# 2023-12-16_LVMi-IonPump-Controller.net
KiCad netlist of a schematic drawn in EAGLE
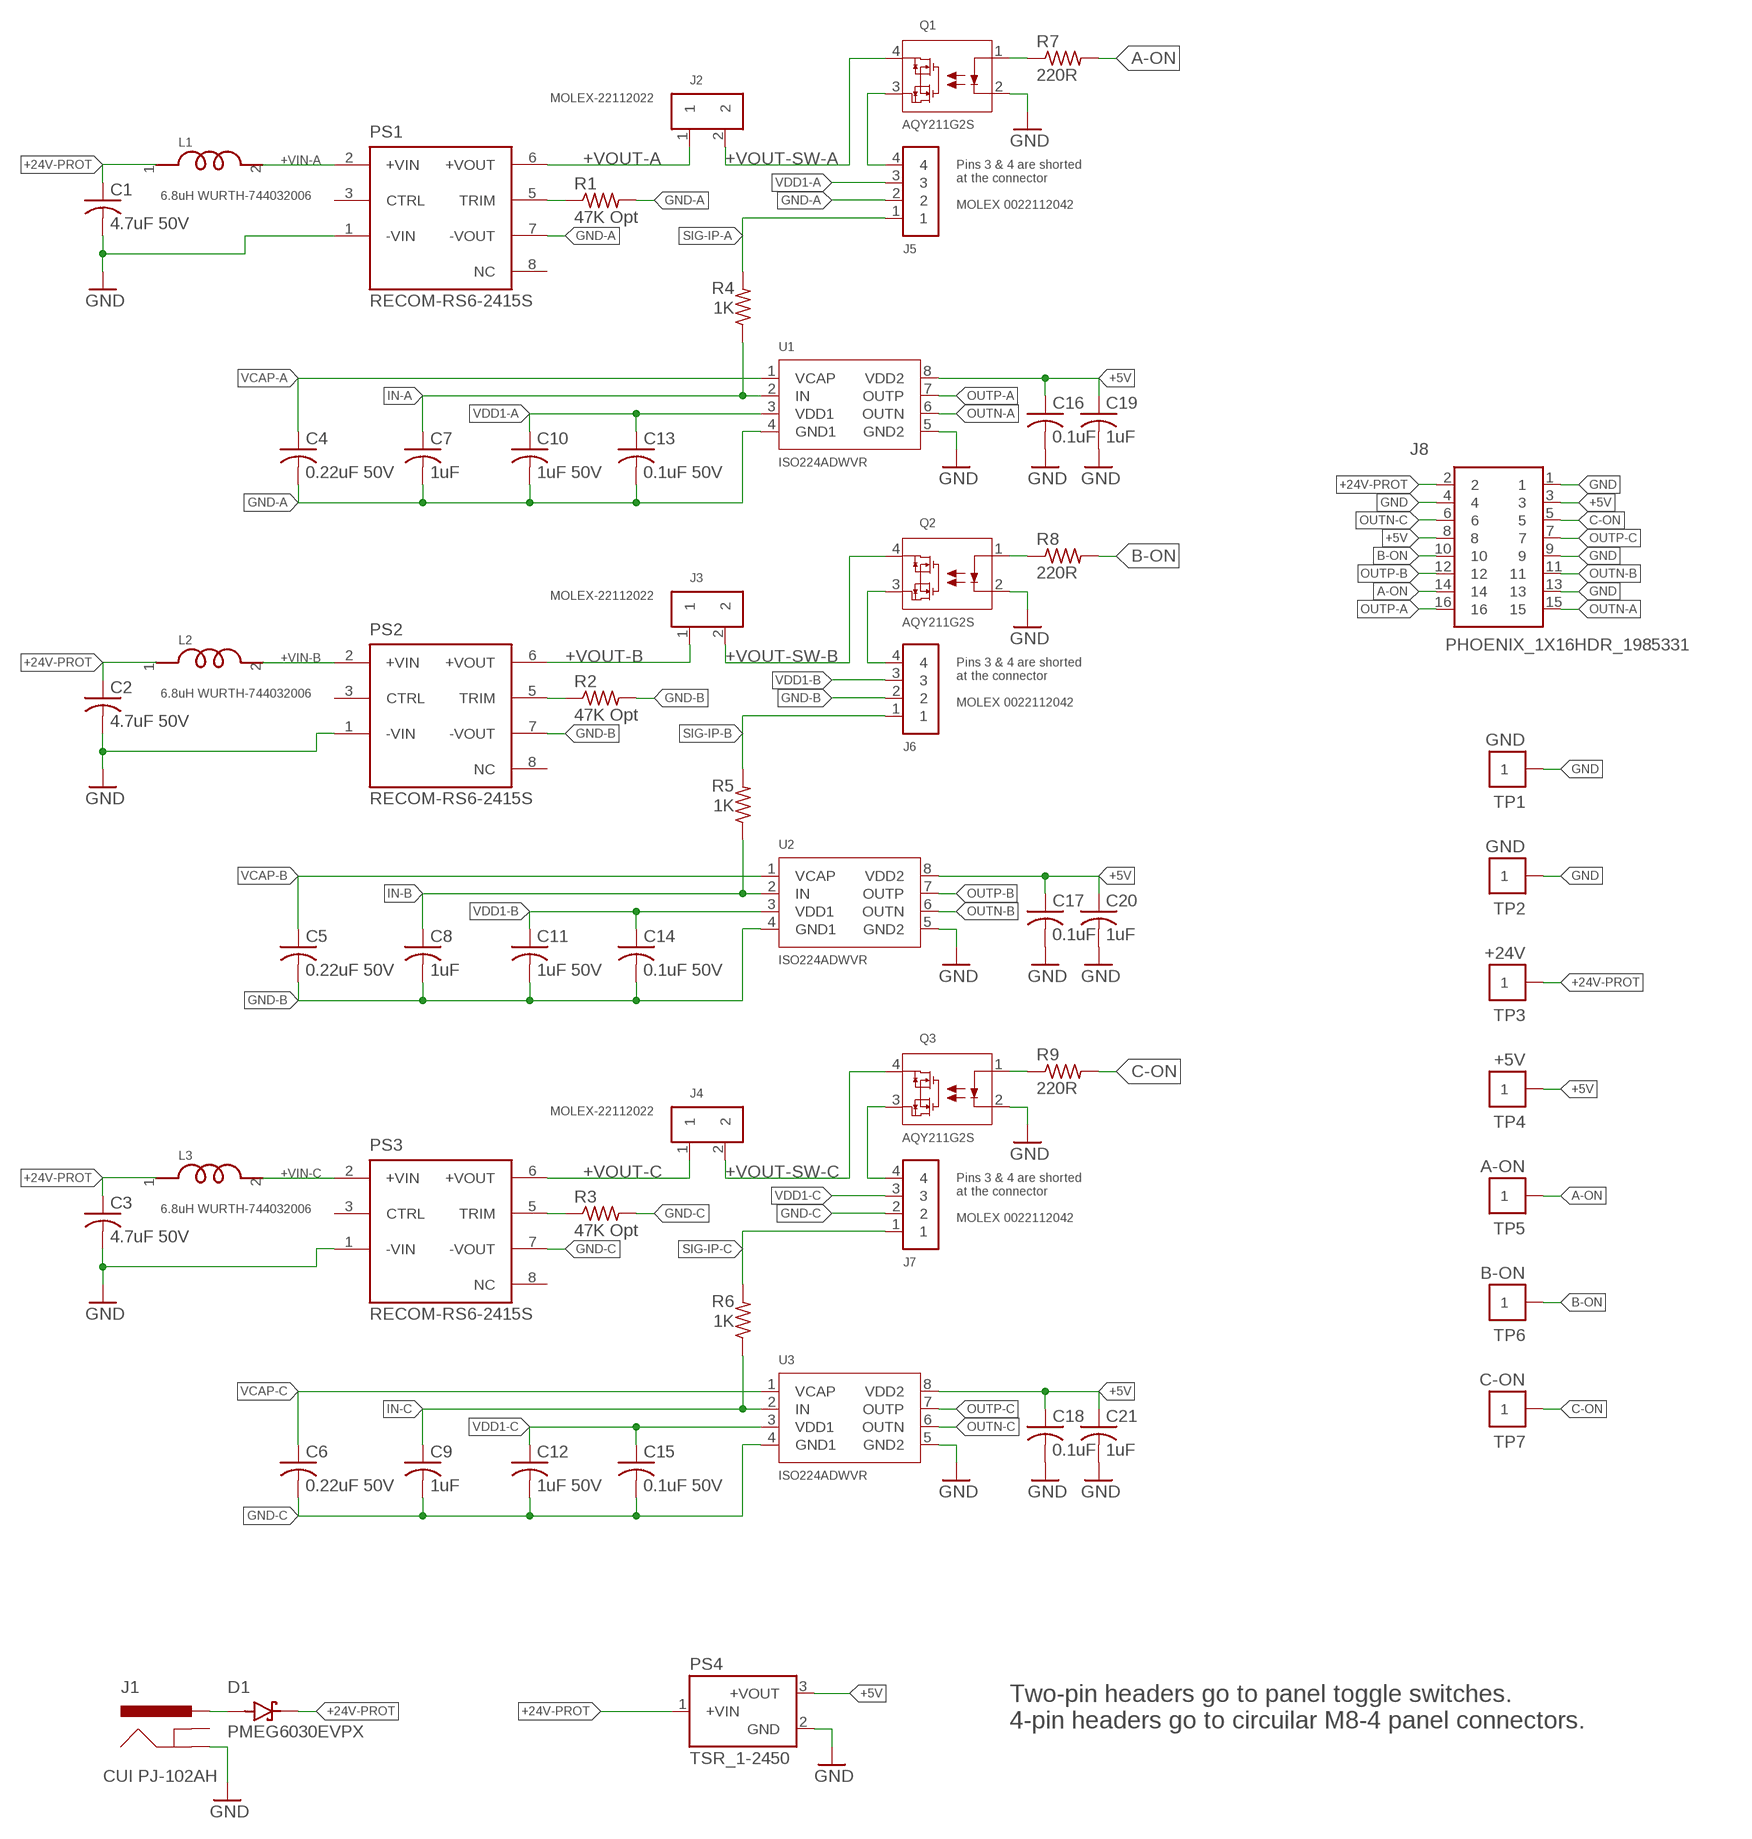
[diagram p0: schematic, sheet 1]

(export (version "E")
  (design (tool "Eeschema 10.0.6"))
  (components
    (comp (ref "C1")
      (value "4.7uF 50V")
      (footprint "eagle-import:C0805")
      (libsource (lib "eagle-import") (part "C-USC0805"))
    )
    (comp (ref "C2")
      (value "4.7uF 50V")
      (footprint "eagle-import:C0805")
      (libsource (lib "eagle-import") (part "C-USC0805"))
    )
    (comp (ref "C3")
      (value "4.7uF 50V")
      (footprint "eagle-import:C0805")
      (libsource (lib "eagle-import") (part "C-USC0805"))
    )
    (comp (ref "C4")
      (value "0.22uF 50V")
      (footprint "eagle-import:C0805")
      (libsource (lib "eagle-import") (part "C-USC0805"))
    )
    (comp (ref "C5")
      (value "0.22uF 50V")
      (footprint "eagle-import:C0805")
      (libsource (lib "eagle-import") (part "C-USC0805"))
    )
    (comp (ref "C6")
      (value "0.22uF 50V")
      (footprint "eagle-import:C0805")
      (libsource (lib "eagle-import") (part "C-USC0805"))
    )
    (comp (ref "C7")
      (value "1uF")
      (footprint "eagle-import:C0805")
      (libsource (lib "eagle-import") (part "C-USC0805"))
    )
    (comp (ref "C8")
      (value "1uF")
      (footprint "eagle-import:C0805")
      (libsource (lib "eagle-import") (part "C-USC0805"))
    )
    (comp (ref "C9")
      (value "1uF")
      (footprint "eagle-import:C0805")
      (libsource (lib "eagle-import") (part "C-USC0805"))
    )
    (comp (ref "C10")
      (value "1uF 50V")
      (footprint "eagle-import:C0805")
      (libsource (lib "eagle-import") (part "C-USC0805"))
    )
    (comp (ref "C11")
      (value "1uF 50V")
      (footprint "eagle-import:C0805")
      (libsource (lib "eagle-import") (part "C-USC0805"))
    )
    (comp (ref "C12")
      (value "1uF 50V")
      (footprint "eagle-import:C0805")
      (libsource (lib "eagle-import") (part "C-USC0805"))
    )
    (comp (ref "C13")
      (value "0.1uF 50V")
      (footprint "eagle-import:C0805")
      (libsource (lib "eagle-import") (part "C-USC0805"))
    )
    (comp (ref "C14")
      (value "0.1uF 50V")
      (footprint "eagle-import:C0805")
      (libsource (lib "eagle-import") (part "C-USC0805"))
    )
    (comp (ref "C15")
      (value "0.1uF 50V")
      (footprint "eagle-import:C0805")
      (libsource (lib "eagle-import") (part "C-USC0805"))
    )
    (comp (ref "C16")
      (value "0.1uF")
      (footprint "eagle-import:C0805")
      (libsource (lib "eagle-import") (part "C-USC0805"))
    )
    (comp (ref "C17")
      (value "0.1uF")
      (footprint "eagle-import:C0805")
      (libsource (lib "eagle-import") (part "C-USC0805"))
    )
    (comp (ref "C18")
      (value "0.1uF")
      (footprint "eagle-import:C0805")
      (libsource (lib "eagle-import") (part "C-USC0805"))
    )
    (comp (ref "C19")
      (value "1uF")
      (footprint "eagle-import:C0805")
      (libsource (lib "eagle-import") (part "C-USC0805"))
    )
    (comp (ref "C20")
      (value "1uF")
      (footprint "eagle-import:C0805")
      (libsource (lib "eagle-import") (part "C-USC0805"))
    )
    (comp (ref "C21")
      (value "1uF")
      (footprint "eagle-import:C0805")
      (libsource (lib "eagle-import") (part "C-USC0805"))
    )
    (comp (ref "D1")
      (value "PMEG6030EVPX")
      (footprint "eagle-import:DIO_PMEG6030EVPX")
      (fields (field (name "DIGI-KEY_PART_NUMBER") "1727-1349-1-ND") (field (name "MF") "Nexperia USA"))
      (libsource (lib "eagle-import") (part "SCHOTTKY-PMEG6030EVPX"))
    )
    (comp (ref "J1")
      (value "CUI PJ-102AH")
      (footprint "eagle-import:PJ-102AH")
      (libsource (lib "eagle-import") (part "POWER_JACKPJ-102AH"))
    )
    (comp (ref "J2")
      (value "MOLEX-22112022")
      (footprint "eagle-import:1X02-MOLEX-22112022")
      (libsource (lib "eagle-import") (part "PINHD-1X2-MOLEX-22112022"))
    )
    (comp (ref "J3")
      (value "MOLEX-22112022")
      (footprint "eagle-import:1X02-MOLEX-22112022")
      (libsource (lib "eagle-import") (part "PINHD-1X2-MOLEX-22112022"))
    )
    (comp (ref "J4")
      (value "MOLEX-22112022")
      (footprint "eagle-import:1X02-MOLEX-22112022")
      (libsource (lib "eagle-import") (part "PINHD-1X2-MOLEX-22112022"))
    )
    (comp (ref "J5")
      (value "MOLEX 0022112042")
      (footprint "eagle-import:1X04-MOLEX-22112042")
      (libsource (lib "eagle-import") (part "PINHD-1X4-MOLEX-22112042"))
    )
    (comp (ref "J6")
      (value "MOLEX 0022112042")
      (footprint "eagle-import:1X04-MOLEX-22112042")
      (libsource (lib "eagle-import") (part "PINHD-1X4-MOLEX-22112042"))
    )
    (comp (ref "J7")
      (value "MOLEX 0022112042")
      (footprint "eagle-import:1X04-MOLEX-22112042")
      (libsource (lib "eagle-import") (part "PINHD-1X4-MOLEX-22112042"))
    )
    (comp (ref "J8")
      (value "PHOENIX_1X16HDR_1985331")
      (footprint "eagle-import:1985331")
      (fields
        (field (name "MANUFACTURER_PART_NUMBER") "1985331")
        (field (name "MOUSER_PART_NUMBER") "651-1985331")
      )
      (libsource (lib "eagle-import") (part "PHOENIX_1X16HDR_1985331"))
    )
    (comp (ref "L1")
      (value "6.8uH WURTH-744032006")
      (footprint "eagle-import:WURTH-1210-INDUCTOR")
      (libsource (lib "eagle-import") (part "INDUCTOR-WURTH-744032006"))
    )
    (comp (ref "L2")
      (value "6.8uH WURTH-744032006")
      (footprint "eagle-import:WURTH-1210-INDUCTOR")
      (libsource (lib "eagle-import") (part "INDUCTOR-WURTH-744032006"))
    )
    (comp (ref "L3")
      (value "6.8uH WURTH-744032006")
      (footprint "eagle-import:WURTH-1210-INDUCTOR")
      (libsource (lib "eagle-import") (part "INDUCTOR-WURTH-744032006"))
    )
    (comp (ref "PS1")
      (value "RECOM-RS6-2415S")
      (footprint "eagle-import:CONV_RS6-2415S")
      (fields
        (field (name "DIGI-KEY_PART_NUMBER") "945-2987-ND")
        (field (name "MF") "Recom Power")
        (field (name "MP") "RS6-2415S")
      )
      (libsource (lib "eagle-import") (part "DC-DC-15V-RECOM-RS6-2415S"))
    )
    (comp (ref "PS2")
      (value "RECOM-RS6-2415S")
      (footprint "eagle-import:CONV_RS6-2415S")
      (fields
        (field (name "DIGI-KEY_PART_NUMBER") "945-2987-ND")
        (field (name "MF") "Recom Power")
        (field (name "MP") "RS6-2415S")
      )
      (libsource (lib "eagle-import") (part "DC-DC-15V-RECOM-RS6-2415S"))
    )
    (comp (ref "PS3")
      (value "RECOM-RS6-2415S")
      (footprint "eagle-import:CONV_RS6-2415S")
      (fields
        (field (name "DIGI-KEY_PART_NUMBER") "945-2987-ND")
        (field (name "MF") "Recom Power")
        (field (name "MP") "RS6-2415S")
      )
      (libsource (lib "eagle-import") (part "DC-DC-15V-RECOM-RS6-2415S"))
    )
    (comp (ref "PS4")
      (value "TSR_1-2450")
      (footprint "eagle-import:CONV_TSR_1-2450")
      (fields (field (name "MANUFACTURER") "Traco Power"))
      (libsource (lib "eagle-import") (part "TSR_1-2450"))
    )
    (comp (ref "Q1")
      (value "AQY211G2S")
      (footprint "eagle-import:SOP4_PAN")
      (fields
        (field (name "MANUFACTURER_PART_NUMBER") "AQY212GSX")
        (field (name "COPYRIGHT") "Copyright (C) 2023 Ultra Librarian. All rights reserved.")
      )
      (libsource (lib "eagle-import") (part "AQY212GSX"))
    )
    (comp (ref "Q2")
      (value "AQY211G2S")
      (footprint "eagle-import:SOP4_PAN")
      (fields
        (field (name "MANUFACTURER_PART_NUMBER") "AQY212GSX")
        (field (name "COPYRIGHT") "Copyright (C) 2023 Ultra Librarian. All rights reserved.")
      )
      (libsource (lib "eagle-import") (part "AQY212GSX"))
    )
    (comp (ref "Q3")
      (value "AQY211G2S")
      (footprint "eagle-import:SOP4_PAN")
      (fields
        (field (name "MANUFACTURER_PART_NUMBER") "AQY212GSX")
        (field (name "COPYRIGHT") "Copyright (C) 2023 Ultra Librarian. All rights reserved.")
      )
      (libsource (lib "eagle-import") (part "AQY212GSX"))
    )
    (comp (ref "R1")
      (value "47K Opt")
      (footprint "eagle-import:R0805")
      (libsource (lib "eagle-import") (part "R-US_R0805"))
    )
    (comp (ref "R2")
      (value "47K Opt")
      (footprint "eagle-import:R0805")
      (libsource (lib "eagle-import") (part "R-US_R0805"))
    )
    (comp (ref "R3")
      (value "47K Opt")
      (footprint "eagle-import:R0805")
      (libsource (lib "eagle-import") (part "R-US_R0805"))
    )
    (comp (ref "R4")
      (value "1K")
      (footprint "eagle-import:R0805")
      (libsource (lib "eagle-import") (part "R-US_R0805"))
    )
    (comp (ref "R5")
      (value "1K")
      (footprint "eagle-import:R0805")
      (libsource (lib "eagle-import") (part "R-US_R0805"))
    )
    (comp (ref "R6")
      (value "1K")
      (footprint "eagle-import:R0805")
      (libsource (lib "eagle-import") (part "R-US_R0805"))
    )
    (comp (ref "R7")
      (value "220R")
      (footprint "eagle-import:R0805")
      (libsource (lib "eagle-import") (part "R-US_R0805"))
    )
    (comp (ref "R8")
      (value "220R")
      (footprint "eagle-import:R0805")
      (libsource (lib "eagle-import") (part "R-US_R0805"))
    )
    (comp (ref "R9")
      (value "220R")
      (footprint "eagle-import:R0805")
      (libsource (lib "eagle-import") (part "R-US_R0805"))
    )
    (comp (ref "TP1")
      (value "GND")
      (footprint "eagle-import:TP5000-TESTPOINT-BLK")
      (libsource (lib "eagle-import") (part "TP5000-TESTPOINT-BLK"))
    )
    (comp (ref "TP2")
      (value "GND")
      (footprint "eagle-import:TP5000-TESTPOINT-BLK")
      (libsource (lib "eagle-import") (part "TP5000-TESTPOINT-BLK"))
    )
    (comp (ref "TP3")
      (value "+24V")
      (footprint "eagle-import:TP5000-TESTPOINT-BLK")
      (libsource (lib "eagle-import") (part "TP5000-TESTPOINT-BLK"))
    )
    (comp (ref "TP4")
      (value "+5V")
      (footprint "eagle-import:TP5000-TESTPOINT-BLK")
      (libsource (lib "eagle-import") (part "TP5000-TESTPOINT-BLK"))
    )
    (comp (ref "TP5")
      (value "A-ON")
      (footprint "eagle-import:TP5000-TESTPOINT-BLK")
      (libsource (lib "eagle-import") (part "TP5000-TESTPOINT-BLK"))
    )
    (comp (ref "TP6")
      (value "B-ON")
      (footprint "eagle-import:TP5000-TESTPOINT-BLK")
      (libsource (lib "eagle-import") (part "TP5000-TESTPOINT-BLK"))
    )
    (comp (ref "TP7")
      (value "C-ON")
      (footprint "eagle-import:TP5000-TESTPOINT-BLK")
      (libsource (lib "eagle-import") (part "TP5000-TESTPOINT-BLK"))
    )
    (comp (ref "U1")
      (value "ISO224ADWVR")
      (footprint "eagle-import:DWV8_TEX")
      (fields (field (name "COPYRIGHT") "Copyright (C) 2018 Accelerated Designs. All rights reserved"))
      (libsource (lib "eagle-import") (part "ISO224ADWVR"))
    )
    (comp (ref "U2")
      (value "ISO224ADWVR")
      (footprint "eagle-import:DWV8_TEX")
      (fields (field (name "COPYRIGHT") "Copyright (C) 2018 Accelerated Designs. All rights reserved"))
      (libsource (lib "eagle-import") (part "ISO224ADWVR"))
    )
    (comp (ref "U3")
      (value "ISO224ADWVR")
      (footprint "eagle-import:DWV8_TEX")
      (fields (field (name "COPYRIGHT") "Copyright (C) 2018 Accelerated Designs. All rights reserved"))
      (libsource (lib "eagle-import") (part "ISO224ADWVR"))
    )
  )
  (nets
    (net (code "1") (name "+5V") (class "Default")
      (node (ref "C16") (pin "1") (pinfunction "1_1") (pintype "passive"))
      (node (ref "C17") (pin "1") (pinfunction "1_1") (pintype "passive"))
      (node (ref "C18") (pin "1") (pinfunction "1_1") (pintype "passive"))
      (node (ref "C19") (pin "1") (pinfunction "1_1") (pintype "passive"))
      (node (ref "C20") (pin "1") (pinfunction "1_1") (pintype "passive"))
      (node (ref "C21") (pin "1") (pinfunction "1_1") (pintype "passive"))
      (node (ref "J8") (pin "3") (pinfunction "3_3") (pintype "bidirectional"))
      (node (ref "J8") (pin "8") (pinfunction "8_8") (pintype "bidirectional"))
      (node (ref "PS4") (pin "3") (pinfunction "+VOUT_3") (pintype "output"))
      (node (ref "TP4") (pin "P$1") (pinfunction "1_P$1") (pintype "bidirectional"))
      (node (ref "U1") (pin "8") (pinfunction "VDD2_8") (pintype "power_in"))
      (node (ref "U2") (pin "8") (pinfunction "VDD2_8") (pintype "power_in"))
      (node (ref "U3") (pin "8") (pinfunction "VDD2_8") (pintype "power_in"))
    )
    (net (code "2") (name "+24V-PROT") (class "Default")
      (node (ref "C1") (pin "1") (pinfunction "1_1") (pintype "passive"))
      (node (ref "C2") (pin "1") (pinfunction "1_1") (pintype "passive"))
      (node (ref "C3") (pin "1") (pinfunction "1_1") (pintype "passive"))
      (node (ref "D1") (pin "1") (pinfunction "K_1") (pintype "passive"))
      (node (ref "J8") (pin "2") (pinfunction "2_2") (pintype "bidirectional"))
      (node (ref "L1") (pin "1") (pinfunction "1_1") (pintype "bidirectional"))
      (node (ref "L2") (pin "1") (pinfunction "1_1") (pintype "bidirectional"))
      (node (ref "L3") (pin "1") (pinfunction "1_1") (pintype "bidirectional"))
      (node (ref "PS4") (pin "1") (pinfunction "+VIN_1") (pintype "input"))
      (node (ref "TP3") (pin "P$1") (pinfunction "1_P$1") (pintype "bidirectional"))
    )
    (net (code "3") (name "/+VIN-A") (class "Default")
      (node (ref "L1") (pin "2") (pinfunction "2_2") (pintype "bidirectional"))
      (node (ref "PS1") (pin "2") (pinfunction "+VIN_2") (pintype "input"))
    )
    (net (code "4") (name "/+VIN-B") (class "Default")
      (node (ref "L2") (pin "2") (pinfunction "2_2") (pintype "bidirectional"))
      (node (ref "PS2") (pin "2") (pinfunction "+VIN_2") (pintype "input"))
    )
    (net (code "5") (name "/+VIN-C") (class "Default")
      (node (ref "L3") (pin "2") (pinfunction "2_2") (pintype "bidirectional"))
      (node (ref "PS3") (pin "2") (pinfunction "+VIN_2") (pintype "input"))
    )
    (net (code "6") (name "/+VOUT-A") (class "Default")
      (node (ref "J2") (pin "1") (pinfunction "1_1") (pintype "bidirectional"))
      (node (ref "PS1") (pin "6") (pinfunction "+VOUT_6") (pintype "output"))
    )
    (net (code "7") (name "/+VOUT-B") (class "Default")
      (node (ref "J3") (pin "1") (pinfunction "1_1") (pintype "bidirectional"))
      (node (ref "PS2") (pin "6") (pinfunction "+VOUT_6") (pintype "output"))
    )
    (net (code "8") (name "/+VOUT-C") (class "Default")
      (node (ref "J4") (pin "1") (pinfunction "1_1") (pintype "bidirectional"))
      (node (ref "PS3") (pin "6") (pinfunction "+VOUT_6") (pintype "output"))
    )
    (net (code "9") (name "/+VOUT-SW-A") (class "Default")
      (node (ref "J2") (pin "2") (pinfunction "2_2") (pintype "bidirectional"))
      (node (ref "Q1") (pin "4") (pinfunction "4_4") (pintype "passive"))
    )
    (net (code "10") (name "/+VOUT-SW-B") (class "Default")
      (node (ref "J3") (pin "2") (pinfunction "2_2") (pintype "bidirectional"))
      (node (ref "Q2") (pin "4") (pinfunction "4_4") (pintype "passive"))
    )
    (net (code "11") (name "/+VOUT-SW-C") (class "Default")
      (node (ref "J4") (pin "2") (pinfunction "2_2") (pintype "bidirectional"))
      (node (ref "Q3") (pin "4") (pinfunction "4_4") (pintype "passive"))
    )
    (net (code "12") (name "A-ON") (class "Default")
      (node (ref "J8") (pin "14") (pinfunction "14_14") (pintype "bidirectional"))
      (node (ref "R7") (pin "2") (pinfunction "2_2") (pintype "passive"))
      (node (ref "TP5") (pin "P$1") (pinfunction "1_P$1") (pintype "bidirectional"))
    )
    (net (code "13") (name "B-ON") (class "Default")
      (node (ref "J8") (pin "10") (pinfunction "10_10") (pintype "bidirectional"))
      (node (ref "R8") (pin "2") (pinfunction "2_2") (pintype "passive"))
      (node (ref "TP6") (pin "P$1") (pinfunction "1_P$1") (pintype "bidirectional"))
    )
    (net (code "14") (name "C-ON") (class "Default")
      (node (ref "J8") (pin "5") (pinfunction "5_5") (pintype "bidirectional"))
      (node (ref "R9") (pin "2") (pinfunction "2_2") (pintype "passive"))
      (node (ref "TP7") (pin "P$1") (pinfunction "1_P$1") (pintype "bidirectional"))
    )
    (net (code "15") (name "GND") (class "Default")
      (node (ref "C1") (pin "2") (pinfunction "2_2") (pintype "passive"))
      (node (ref "C16") (pin "2") (pinfunction "2_2") (pintype "passive"))
      (node (ref "C17") (pin "2") (pinfunction "2_2") (pintype "passive"))
      (node (ref "C18") (pin "2") (pinfunction "2_2") (pintype "passive"))
      (node (ref "C19") (pin "2") (pinfunction "2_2") (pintype "passive"))
      (node (ref "C2") (pin "2") (pinfunction "2_2") (pintype "passive"))
      (node (ref "C20") (pin "2") (pinfunction "2_2") (pintype "passive"))
      (node (ref "C21") (pin "2") (pinfunction "2_2") (pintype "passive"))
      (node (ref "C3") (pin "2") (pinfunction "2_2") (pintype "passive"))
      (node (ref "J1") (pin "GND") (pinfunction "GND_GND") (pintype "bidirectional"))
      (node (ref "J8") (pin "1") (pinfunction "1_1") (pintype "bidirectional"))
      (node (ref "J8") (pin "13") (pinfunction "13_13") (pintype "bidirectional"))
      (node (ref "J8") (pin "4") (pinfunction "4_4") (pintype "bidirectional"))
      (node (ref "J8") (pin "9") (pinfunction "9_9") (pintype "bidirectional"))
      (node (ref "PS1") (pin "1") (pinfunction "-VIN_1") (pintype "input"))
      (node (ref "PS2") (pin "1") (pinfunction "-VIN_1") (pintype "input"))
      (node (ref "PS3") (pin "1") (pinfunction "-VIN_1") (pintype "input"))
      (node (ref "PS4") (pin "2") (pinfunction "GND_2") (pintype "power_in"))
      (node (ref "Q1") (pin "2") (pinfunction "2_2") (pintype "passive"))
      (node (ref "Q2") (pin "2") (pinfunction "2_2") (pintype "passive"))
      (node (ref "Q3") (pin "2") (pinfunction "2_2") (pintype "passive"))
      (node (ref "TP1") (pin "P$1") (pinfunction "1_P$1") (pintype "bidirectional"))
      (node (ref "TP2") (pin "P$1") (pinfunction "1_P$1") (pintype "bidirectional"))
      (node (ref "U1") (pin "5") (pinfunction "GND2_5") (pintype "power_in"))
      (node (ref "U2") (pin "5") (pinfunction "GND2_5") (pintype "power_in"))
      (node (ref "U3") (pin "5") (pinfunction "GND2_5") (pintype "power_in"))
    )
    (net (code "16") (name "GND-A") (class "Default")
      (node (ref "C10") (pin "2") (pinfunction "2_2") (pintype "passive"))
      (node (ref "C13") (pin "2") (pinfunction "2_2") (pintype "passive"))
      (node (ref "C4") (pin "2") (pinfunction "2_2") (pintype "passive"))
      (node (ref "C7") (pin "2") (pinfunction "2_2") (pintype "passive"))
      (node (ref "J5") (pin "2") (pinfunction "2_2") (pintype "bidirectional"))
      (node (ref "PS1") (pin "7") (pinfunction "-VOUT_7") (pintype "output"))
      (node (ref "R1") (pin "2") (pinfunction "2_2") (pintype "passive"))
      (node (ref "U1") (pin "4") (pinfunction "GND1_4") (pintype "power_in"))
    )
    (net (code "17") (name "GND-B") (class "Default")
      (node (ref "C11") (pin "2") (pinfunction "2_2") (pintype "passive"))
      (node (ref "C14") (pin "2") (pinfunction "2_2") (pintype "passive"))
      (node (ref "C5") (pin "2") (pinfunction "2_2") (pintype "passive"))
      (node (ref "C8") (pin "2") (pinfunction "2_2") (pintype "passive"))
      (node (ref "J6") (pin "2") (pinfunction "2_2") (pintype "bidirectional"))
      (node (ref "PS2") (pin "7") (pinfunction "-VOUT_7") (pintype "output"))
      (node (ref "R2") (pin "2") (pinfunction "2_2") (pintype "passive"))
      (node (ref "U2") (pin "4") (pinfunction "GND1_4") (pintype "power_in"))
    )
    (net (code "18") (name "GND-C") (class "Default")
      (node (ref "C12") (pin "2") (pinfunction "2_2") (pintype "passive"))
      (node (ref "C15") (pin "2") (pinfunction "2_2") (pintype "passive"))
      (node (ref "C6") (pin "2") (pinfunction "2_2") (pintype "passive"))
      (node (ref "C9") (pin "2") (pinfunction "2_2") (pintype "passive"))
      (node (ref "J7") (pin "2") (pinfunction "2_2") (pintype "bidirectional"))
      (node (ref "PS3") (pin "7") (pinfunction "-VOUT_7") (pintype "output"))
      (node (ref "R3") (pin "2") (pinfunction "2_2") (pintype "passive"))
      (node (ref "U3") (pin "4") (pinfunction "GND1_4") (pintype "power_in"))
    )
    (net (code "19") (name "IN-A") (class "Default")
      (node (ref "C7") (pin "1") (pinfunction "1_1") (pintype "passive"))
      (node (ref "R4") (pin "1") (pinfunction "1_1") (pintype "passive"))
      (node (ref "U1") (pin "2") (pinfunction "IN_2") (pintype "input"))
    )
    (net (code "20") (name "IN-B") (class "Default")
      (node (ref "C8") (pin "1") (pinfunction "1_1") (pintype "passive"))
      (node (ref "R5") (pin "1") (pinfunction "1_1") (pintype "passive"))
      (node (ref "U2") (pin "2") (pinfunction "IN_2") (pintype "input"))
    )
    (net (code "21") (name "IN-C") (class "Default")
      (node (ref "C9") (pin "1") (pinfunction "1_1") (pintype "passive"))
      (node (ref "R6") (pin "1") (pinfunction "1_1") (pintype "passive"))
      (node (ref "U3") (pin "2") (pinfunction "IN_2") (pintype "input"))
    )
    (net (code "22") (name "Net-(D1-A)") (class "Default")
      (node (ref "D1") (pin "2") (pinfunction "A_2") (pintype "passive"))
      (node (ref "J1") (pin "PWR") (pinfunction "PWR_PWR") (pintype "bidirectional"))
    )
    (net (code "23") (name "Net-(J5-Pad4)") (class "Default")
      (node (ref "J5") (pin "4") (pinfunction "4_4") (pintype "bidirectional"))
      (node (ref "Q1") (pin "3") (pinfunction "3_3") (pintype "passive"))
    )
    (net (code "24") (name "Net-(J6-Pad4)") (class "Default")
      (node (ref "J6") (pin "4") (pinfunction "4_4") (pintype "bidirectional"))
      (node (ref "Q2") (pin "3") (pinfunction "3_3") (pintype "passive"))
    )
    (net (code "25") (name "Net-(J7-Pad4)") (class "Default")
      (node (ref "J7") (pin "4") (pinfunction "4_4") (pintype "bidirectional"))
      (node (ref "Q3") (pin "3") (pinfunction "3_3") (pintype "passive"))
    )
    (net (code "26") (name "Net-(PS1-TRIM)") (class "Default")
      (node (ref "PS1") (pin "5") (pinfunction "TRIM_5") (pintype "passive"))
      (node (ref "R1") (pin "1") (pinfunction "1_1") (pintype "passive"))
    )
    (net (code "27") (name "Net-(PS2-TRIM)") (class "Default")
      (node (ref "PS2") (pin "5") (pinfunction "TRIM_5") (pintype "passive"))
      (node (ref "R2") (pin "1") (pinfunction "1_1") (pintype "passive"))
    )
    (net (code "28") (name "Net-(PS3-TRIM)") (class "Default")
      (node (ref "PS3") (pin "5") (pinfunction "TRIM_5") (pintype "passive"))
      (node (ref "R3") (pin "1") (pinfunction "1_1") (pintype "passive"))
    )
    (net (code "29") (name "Net-(Q1-Pad1)") (class "Default")
      (node (ref "Q1") (pin "1") (pinfunction "1_1") (pintype "passive"))
      (node (ref "R7") (pin "1") (pinfunction "1_1") (pintype "passive"))
    )
    (net (code "30") (name "Net-(Q2-Pad1)") (class "Default")
      (node (ref "Q2") (pin "1") (pinfunction "1_1") (pintype "passive"))
      (node (ref "R8") (pin "1") (pinfunction "1_1") (pintype "passive"))
    )
    (net (code "31") (name "Net-(Q3-Pad1)") (class "Default")
      (node (ref "Q3") (pin "1") (pinfunction "1_1") (pintype "passive"))
      (node (ref "R9") (pin "1") (pinfunction "1_1") (pintype "passive"))
    )
    (net (code "32") (name "OUTN-A") (class "Default")
      (node (ref "J8") (pin "15") (pinfunction "15_15") (pintype "bidirectional"))
      (node (ref "U1") (pin "6") (pinfunction "OUTN_6") (pintype "output"))
    )
    (net (code "33") (name "OUTN-B") (class "Default")
      (node (ref "J8") (pin "11") (pinfunction "11_11") (pintype "bidirectional"))
      (node (ref "U2") (pin "6") (pinfunction "OUTN_6") (pintype "output"))
    )
    (net (code "34") (name "OUTN-C") (class "Default")
      (node (ref "J8") (pin "6") (pinfunction "6_6") (pintype "bidirectional"))
      (node (ref "U3") (pin "6") (pinfunction "OUTN_6") (pintype "output"))
    )
    (net (code "35") (name "OUTP-A") (class "Default")
      (node (ref "J8") (pin "16") (pinfunction "16_16") (pintype "bidirectional"))
      (node (ref "U1") (pin "7") (pinfunction "OUTP_7") (pintype "output"))
    )
    (net (code "36") (name "OUTP-B") (class "Default")
      (node (ref "J8") (pin "12") (pinfunction "12_12") (pintype "bidirectional"))
      (node (ref "U2") (pin "7") (pinfunction "OUTP_7") (pintype "output"))
    )
    (net (code "37") (name "OUTP-C") (class "Default")
      (node (ref "J8") (pin "7") (pinfunction "7_7") (pintype "bidirectional"))
      (node (ref "U3") (pin "7") (pinfunction "OUTP_7") (pintype "output"))
    )
    (net (code "38") (name "SIG-IP-A") (class "Default")
      (node (ref "J5") (pin "1") (pinfunction "1_1") (pintype "bidirectional"))
      (node (ref "R4") (pin "2") (pinfunction "2_2") (pintype "passive"))
    )
    (net (code "39") (name "SIG-IP-B") (class "Default")
      (node (ref "J6") (pin "1") (pinfunction "1_1") (pintype "bidirectional"))
      (node (ref "R5") (pin "2") (pinfunction "2_2") (pintype "passive"))
    )
    (net (code "40") (name "SIG-IP-C") (class "Default")
      (node (ref "J7") (pin "1") (pinfunction "1_1") (pintype "bidirectional"))
      (node (ref "R6") (pin "2") (pinfunction "2_2") (pintype "passive"))
    )
    (net (code "41") (name "VCAP-A") (class "Default")
      (node (ref "C4") (pin "1") (pinfunction "1_1") (pintype "passive"))
      (node (ref "U1") (pin "1") (pinfunction "VCAP_1") (pintype "power_in"))
    )
    (net (code "42") (name "VCAP-B") (class "Default")
      (node (ref "C5") (pin "1") (pinfunction "1_1") (pintype "passive"))
      (node (ref "U2") (pin "1") (pinfunction "VCAP_1") (pintype "power_in"))
    )
    (net (code "43") (name "VCAP-C") (class "Default")
      (node (ref "C6") (pin "1") (pinfunction "1_1") (pintype "passive"))
      (node (ref "U3") (pin "1") (pinfunction "VCAP_1") (pintype "power_in"))
    )
    (net (code "44") (name "VDD1-A") (class "Default")
      (node (ref "C10") (pin "1") (pinfunction "1_1") (pintype "passive"))
      (node (ref "C13") (pin "1") (pinfunction "1_1") (pintype "passive"))
      (node (ref "J5") (pin "3") (pinfunction "3_3") (pintype "bidirectional"))
      (node (ref "U1") (pin "3") (pinfunction "VDD1_3") (pintype "power_in"))
    )
    (net (code "45") (name "VDD1-B") (class "Default")
      (node (ref "C11") (pin "1") (pinfunction "1_1") (pintype "passive"))
      (node (ref "C14") (pin "1") (pinfunction "1_1") (pintype "passive"))
      (node (ref "J6") (pin "3") (pinfunction "3_3") (pintype "bidirectional"))
      (node (ref "U2") (pin "3") (pinfunction "VDD1_3") (pintype "power_in"))
    )
    (net (code "46") (name "VDD1-C") (class "Default")
      (node (ref "C12") (pin "1") (pinfunction "1_1") (pintype "passive"))
      (node (ref "C15") (pin "1") (pinfunction "1_1") (pintype "passive"))
      (node (ref "J7") (pin "3") (pinfunction "3_3") (pintype "bidirectional"))
      (node (ref "U3") (pin "3") (pinfunction "VDD1_3") (pintype "power_in"))
    )
    (net (code "47") (name "unconnected-(J1-GNDBREAK-PadGNDBRK)") (class "Default")
      (node (ref "J1") (pin "GNDBRK") (pinfunction "GNDBREAK_GNDBRK") (pintype "bidirectional"))
    )
    (net (code "48") (name "unconnected-(PS1-CTRL-Pad3)") (class "Default")
      (node (ref "PS1") (pin "3") (pinfunction "CTRL_3") (pintype "input"))
    )
    (net (code "49") (name "unconnected-(PS1-NC-Pad8)") (class "Default")
      (node (ref "PS1") (pin "8") (pinfunction "NC_8") (pintype "no_connect"))
    )
    (net (code "50") (name "unconnected-(PS2-CTRL-Pad3)") (class "Default")
      (node (ref "PS2") (pin "3") (pinfunction "CTRL_3") (pintype "input"))
    )
    (net (code "51") (name "unconnected-(PS2-NC-Pad8)") (class "Default")
      (node (ref "PS2") (pin "8") (pinfunction "NC_8") (pintype "no_connect"))
    )
    (net (code "52") (name "unconnected-(PS3-CTRL-Pad3)") (class "Default")
      (node (ref "PS3") (pin "3") (pinfunction "CTRL_3") (pintype "input"))
    )
    (net (code "53") (name "unconnected-(PS3-NC-Pad8)") (class "Default")
      (node (ref "PS3") (pin "8") (pinfunction "NC_8") (pintype "no_connect"))
    )
  )
)
